# R2P_BLDC_module.net
KiCad netlist of a schematic drawn in EAGLE
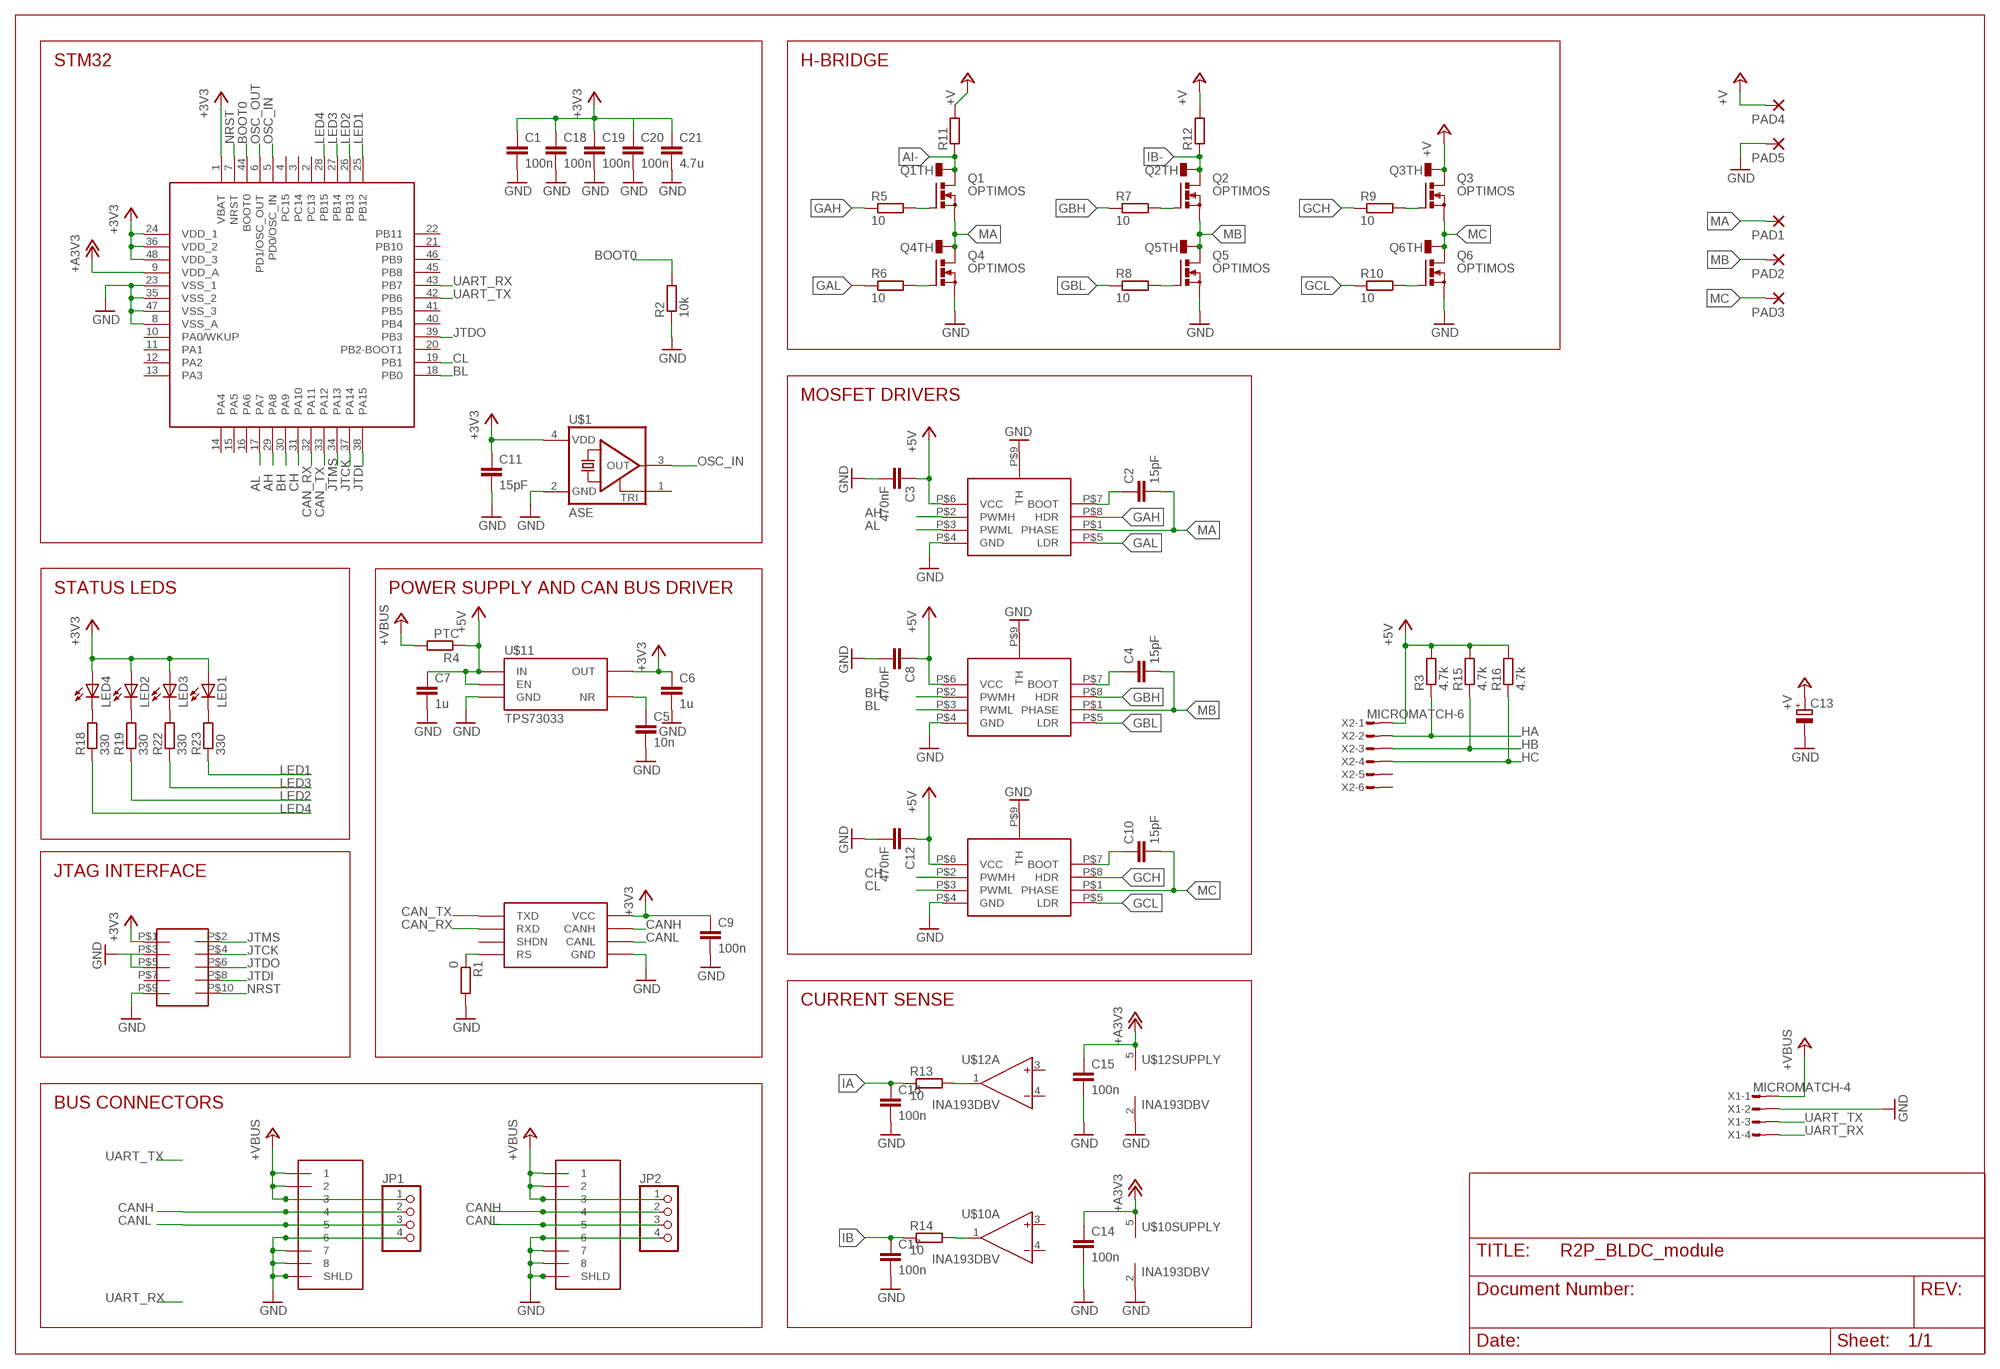
[diagram p0: schematic, sheet 1]

(export (version "E")
  (design (tool "Eeschema 10.0.6"))
  (components
    (comp (ref "1")
      (value "RJ45-43860")
      (footprint "eagle-import:0438600010")
      (libsource (lib "eagle-import") (part "RJ45-43860"))
    )
    (comp (ref "2")
      (value "RJ45-43860")
      (footprint "eagle-import:0438600010")
      (libsource (lib "eagle-import") (part "RJ45-43860"))
    )
    (comp (ref "C1")
      (value "100n")
      (footprint "eagle-import:C0603")
      (libsource (lib "eagle-import") (part "C-EUC0603"))
    )
    (comp (ref "C2")
      (value "15pF")
      (footprint "eagle-import:C0603")
      (libsource (lib "eagle-import") (part "C-EUC0603"))
    )
    (comp (ref "C3")
      (value "470nF")
      (footprint "eagle-import:C0603")
      (libsource (lib "eagle-import") (part "C-EUC0603"))
    )
    (comp (ref "C4")
      (value "15pF")
      (footprint "eagle-import:C0603")
      (libsource (lib "eagle-import") (part "C-EUC0603"))
    )
    (comp (ref "C5")
      (value "10n")
      (footprint "eagle-import:C0603")
      (libsource (lib "eagle-import") (part "C-EUC0603"))
    )
    (comp (ref "C6")
      (value "1u")
      (footprint "eagle-import:C0603")
      (libsource (lib "eagle-import") (part "C-EUC0603"))
    )
    (comp (ref "C7")
      (value "1u")
      (footprint "eagle-import:C0603")
      (libsource (lib "eagle-import") (part "C-EUC0603"))
    )
    (comp (ref "C8")
      (value "470nF")
      (footprint "eagle-import:C0603")
      (libsource (lib "eagle-import") (part "C-EUC0603"))
    )
    (comp (ref "C9")
      (value "100n")
      (footprint "eagle-import:C0603")
      (libsource (lib "eagle-import") (part "C-EUC0603"))
    )
    (comp (ref "C10")
      (value "15pF")
      (footprint "eagle-import:C0603")
      (libsource (lib "eagle-import") (part "C-EUC0603"))
    )
    (comp (ref "C11")
      (value "15pF")
      (footprint "eagle-import:C0603")
      (libsource (lib "eagle-import") (part "C-EUC0603"))
    )
    (comp (ref "C12")
      (value "470nF")
      (footprint "eagle-import:C0603")
      (libsource (lib "eagle-import") (part "C-EUC0603"))
    )
    (comp (ref "C13")
      (value "CPOL-EUE35-12AXIAL")
      (footprint "eagle-import:E35-12")
      (libsource (lib "eagle-import") (part "CPOL-EUE35-12AXIAL"))
    )
    (comp (ref "C14")
      (value "100n")
      (footprint "eagle-import:C0603")
      (libsource (lib "eagle-import") (part "C-EUC0603"))
    )
    (comp (ref "C15")
      (value "100n")
      (footprint "eagle-import:C0603")
      (libsource (lib "eagle-import") (part "C-EUC0603"))
    )
    (comp (ref "C16")
      (value "100n")
      (footprint "eagle-import:C0603")
      (libsource (lib "eagle-import") (part "C-EUC0603"))
    )
    (comp (ref "C17")
      (value "100n")
      (footprint "eagle-import:C0603")
      (libsource (lib "eagle-import") (part "C-EUC0603"))
    )
    (comp (ref "C18")
      (value "100n")
      (footprint "eagle-import:C0603")
      (libsource (lib "eagle-import") (part "C-EUC0603"))
    )
    (comp (ref "C19")
      (value "100n")
      (footprint "eagle-import:C0603")
      (libsource (lib "eagle-import") (part "C-EUC0603"))
    )
    (comp (ref "C20")
      (value "100n")
      (footprint "eagle-import:C0603")
      (libsource (lib "eagle-import") (part "C-EUC0603"))
    )
    (comp (ref "C21")
      (value "4.7u")
      (footprint "eagle-import:C0805")
      (libsource (lib "eagle-import") (part "C-EUC0805"))
    )
    (comp (ref "JP1")
      (value "PINHD-1X4")
      (footprint "eagle-import:1X04")
      (libsource (lib "eagle-import") (part "PINHD-1X4"))
    )
    (comp (ref "JP2")
      (value "PINHD-1X4")
      (footprint "eagle-import:1X04")
      (libsource (lib "eagle-import") (part "PINHD-1X4"))
    )
    (comp (ref "LED1")
      (value "LEDCHIPLED_0805")
      (footprint "eagle-import:CHIPLED_0805")
      (libsource (lib "eagle-import") (part "LEDCHIPLED_0805"))
    )
    (comp (ref "LED2")
      (value "LEDCHIPLED_0805")
      (footprint "eagle-import:CHIPLED_0805")
      (libsource (lib "eagle-import") (part "LEDCHIPLED_0805"))
    )
    (comp (ref "LED3")
      (value "LEDCHIPLED_0805")
      (footprint "eagle-import:CHIPLED_0805")
      (libsource (lib "eagle-import") (part "LEDCHIPLED_0805"))
    )
    (comp (ref "LED4")
      (value "LEDCHIPLED_0805")
      (footprint "eagle-import:CHIPLED_0805")
      (libsource (lib "eagle-import") (part "LEDCHIPLED_0805"))
    )
    (comp (ref "PAD1")
      (value "3,81/1,4")
      (footprint "eagle-import:3,81_1,4")
      (libsource (lib "eagle-import") (part "3,81/1,4"))
    )
    (comp (ref "PAD2")
      (value "3,81/1,4")
      (footprint "eagle-import:3,81_1,4")
      (libsource (lib "eagle-import") (part "3,81/1,4"))
    )
    (comp (ref "PAD3")
      (value "3,81/1,4")
      (footprint "eagle-import:3,81_1,4")
      (libsource (lib "eagle-import") (part "3,81/1,4"))
    )
    (comp (ref "PAD4")
      (value "3,81/1,4")
      (footprint "eagle-import:3,81_1,4")
      (libsource (lib "eagle-import") (part "3,81/1,4"))
    )
    (comp (ref "PAD5")
      (value "3,81/1,4")
      (footprint "eagle-import:3,81_1,4")
      (libsource (lib "eagle-import") (part "3,81/1,4"))
    )
    (comp (ref "Q1")
      (value "OPTIMOS")
      (footprint "eagle-import:PG-TDSON-8")
      (libsource (lib "eagle-import") (part "OPTIMOS"))
    )
    (comp (ref "Q2")
      (value "OPTIMOS")
      (footprint "eagle-import:PG-TDSON-8")
      (libsource (lib "eagle-import") (part "OPTIMOS"))
    )
    (comp (ref "Q3")
      (value "OPTIMOS")
      (footprint "eagle-import:PG-TDSON-8")
      (libsource (lib "eagle-import") (part "OPTIMOS"))
    )
    (comp (ref "Q4")
      (value "OPTIMOS")
      (footprint "eagle-import:PG-TDSON-8")
      (libsource (lib "eagle-import") (part "OPTIMOS"))
    )
    (comp (ref "Q5")
      (value "OPTIMOS")
      (footprint "eagle-import:PG-TDSON-8")
      (libsource (lib "eagle-import") (part "OPTIMOS"))
    )
    (comp (ref "Q6")
      (value "OPTIMOS")
      (footprint "eagle-import:PG-TDSON-8")
      (libsource (lib "eagle-import") (part "OPTIMOS"))
    )
    (comp (ref "R1")
      (value "0")
      (footprint "eagle-import:R0603")
      (libsource (lib "eagle-import") (part "R-EU_R0603"))
    )
    (comp (ref "R2")
      (value "10k")
      (footprint "eagle-import:R0603")
      (libsource (lib "eagle-import") (part "R-EU_R0603"))
    )
    (comp (ref "R3")
      (value "4.7k")
      (footprint "eagle-import:R0603")
      (libsource (lib "eagle-import") (part "R-EU_R0603"))
    )
    (comp (ref "R4")
      (value "PTC")
      (footprint "eagle-import:R0805")
      (libsource (lib "eagle-import") (part "R-EU_R0805"))
    )
    (comp (ref "R5")
      (value "10")
      (footprint "eagle-import:R0603")
      (libsource (lib "eagle-import") (part "R-EU_R0603"))
    )
    (comp (ref "R6")
      (value "10")
      (footprint "eagle-import:R0603")
      (libsource (lib "eagle-import") (part "R-EU_R0603"))
    )
    (comp (ref "R7")
      (value "10")
      (footprint "eagle-import:R0603")
      (libsource (lib "eagle-import") (part "R-EU_R0603"))
    )
    (comp (ref "R8")
      (value "10")
      (footprint "eagle-import:R0603")
      (libsource (lib "eagle-import") (part "R-EU_R0603"))
    )
    (comp (ref "R9")
      (value "10")
      (footprint "eagle-import:R0603")
      (libsource (lib "eagle-import") (part "R-EU_R0603"))
    )
    (comp (ref "R10")
      (value "10")
      (footprint "eagle-import:R0603")
      (libsource (lib "eagle-import") (part "R-EU_R0603"))
    )
    (comp (ref "R11")
      (value "R-EU_R1206")
      (footprint "eagle-import:R1206")
      (libsource (lib "eagle-import") (part "R-EU_R1206"))
    )
    (comp (ref "R12")
      (value "R-EU_R1206")
      (footprint "eagle-import:R1206")
      (libsource (lib "eagle-import") (part "R-EU_R1206"))
    )
    (comp (ref "R13")
      (value "10")
      (footprint "eagle-import:R0603")
      (libsource (lib "eagle-import") (part "R-EU_R0603"))
    )
    (comp (ref "R14")
      (value "10")
      (footprint "eagle-import:R0603")
      (libsource (lib "eagle-import") (part "R-EU_R0603"))
    )
    (comp (ref "R15")
      (value "4.7k")
      (footprint "eagle-import:R0603")
      (libsource (lib "eagle-import") (part "R-EU_R0603"))
    )
    (comp (ref "R16")
      (value "4.7k")
      (footprint "eagle-import:R0603")
      (libsource (lib "eagle-import") (part "R-EU_R0603"))
    )
    (comp (ref "R18")
      (value "330")
      (footprint "eagle-import:R0603")
      (libsource (lib "eagle-import") (part "R-EU_R0603"))
    )
    (comp (ref "R19")
      (value "330")
      (footprint "eagle-import:R0603")
      (libsource (lib "eagle-import") (part "R-EU_R0603"))
    )
    (comp (ref "R22")
      (value "330")
      (footprint "eagle-import:R0603")
      (libsource (lib "eagle-import") (part "R-EU_R0603"))
    )
    (comp (ref "R23")
      (value "330")
      (footprint "eagle-import:R0603")
      (libsource (lib "eagle-import") (part "R-EU_R0603"))
    )
    (comp (ref "SOT1")
      (value "MAX3051")
      (footprint "eagle-import:SOT23-8L")
      (libsource (lib "eagle-import") (part "MAX3051"))
    )
    (comp (ref "U$1")
      (value "ASE")
      (footprint "eagle-import:ASE")
      (libsource (lib "eagle-import") (part "ASE"))
    )
    (comp (ref "U$2")
      (value "MCP14700MF")
      (footprint "eagle-import:DFN8")
      (libsource (lib "eagle-import") (part "MCP14700MF"))
    )
    (comp (ref "U$4")
      (value "FTSH-105")
      (footprint "eagle-import:FTSH-105")
      (libsource (lib "eagle-import") (part "FTSH-105"))
    )
    (comp (ref "U$8")
      (value "MCP14700MF")
      (footprint "eagle-import:DFN8")
      (libsource (lib "eagle-import") (part "MCP14700MF"))
    )
    (comp (ref "U$9")
      (value "MCP14700MF")
      (footprint "eagle-import:DFN8")
      (libsource (lib "eagle-import") (part "MCP14700MF"))
    )
    (comp (ref "U$10")
      (value "INA193DBV")
      (footprint "eagle-import:SOT23-5L")
      (libsource (lib "eagle-import") (part "INA193DBV"))
    )
    (comp (ref "U$11")
      (value "TPS73033")
      (footprint "eagle-import:SOT23-5L")
      (libsource (lib "eagle-import") (part "TPS73033"))
    )
    (comp (ref "U$12")
      (value "INA193DBV")
      (footprint "eagle-import:SOT23-5L")
      (libsource (lib "eagle-import") (part "INA193DBV"))
    )
    (comp (ref "U1")
      (value "STM32F103CX")
      (footprint "eagle-import:LQFP48")
      (libsource (lib "eagle-import") (part "STM32F103CX"))
    )
    (comp (ref "X1")
      (value "MICROMATCH-4")
      (footprint "eagle-import:MICROMATCH-4")
      (libsource (lib "eagle-import") (part "MICROMATCH-4"))
    )
    (comp (ref "X2")
      (value "MICROMATCH-6")
      (footprint "eagle-import:MICROMATCH-6")
      (libsource (lib "eagle-import") (part "MICROMATCH-6"))
    )
  )
  (nets
    (net (code "1") (name "+3V3") (class "Default")
      (node (ref "C1") (pin "1") (pinfunction "1_1") (pintype "passive"))
      (node (ref "C11") (pin "1") (pinfunction "1_1") (pintype "passive"))
      (node (ref "C18") (pin "1") (pinfunction "1_1") (pintype "passive"))
      (node (ref "C19") (pin "1") (pinfunction "1_1") (pintype "passive"))
      (node (ref "C20") (pin "1") (pinfunction "1_1") (pintype "passive"))
      (node (ref "C21") (pin "1") (pinfunction "1_1") (pintype "passive"))
      (node (ref "C6") (pin "1") (pinfunction "1_1") (pintype "passive"))
      (node (ref "C9") (pin "1") (pinfunction "1_1") (pintype "passive"))
      (node (ref "LED1") (pin "A") (pinfunction "A_A") (pintype "passive"))
      (node (ref "LED2") (pin "A") (pinfunction "A_A") (pintype "passive"))
      (node (ref "LED3") (pin "A") (pinfunction "A_A") (pintype "passive"))
      (node (ref "LED4") (pin "A") (pinfunction "A_A") (pintype "passive"))
      (node (ref "SOT1") (pin "P$3") (pinfunction "VCC_P$3") (pintype "bidirectional"))
      (node (ref "U$1") (pin "4") (pinfunction "VDD_4") (pintype "power_in"))
      (node (ref "U$11") (pin "5") (pinfunction "OUT_5") (pintype "power_in"))
      (node (ref "U$4") (pin "P$1") (pinfunction "P$1_P$1") (pintype "bidirectional"))
      (node (ref "U1") (pin "1") (pinfunction "VBAT_1") (pintype "bidirectional"))
      (node (ref "U1") (pin "24") (pinfunction "VDD_1_24") (pintype "bidirectional"))
      (node (ref "U1") (pin "36") (pinfunction "VDD_2_36") (pintype "bidirectional"))
      (node (ref "U1") (pin "48") (pinfunction "VDD_3_48") (pintype "bidirectional"))
    )
    (net (code "2") (name "+5V") (class "Default")
      (node (ref "C12") (pin "1") (pinfunction "1_1") (pintype "passive"))
      (node (ref "C3") (pin "1") (pinfunction "1_1") (pintype "passive"))
      (node (ref "C7") (pin "1") (pinfunction "1_1") (pintype "passive"))
      (node (ref "C8") (pin "1") (pinfunction "1_1") (pintype "passive"))
      (node (ref "R15") (pin "2") (pinfunction "2_2") (pintype "passive"))
      (node (ref "R16") (pin "2") (pinfunction "2_2") (pintype "passive"))
      (node (ref "R3") (pin "2") (pinfunction "2_2") (pintype "passive"))
      (node (ref "R4") (pin "1") (pinfunction "1_1") (pintype "passive"))
      (node (ref "U$11") (pin "1") (pinfunction "IN_1") (pintype "power_in"))
      (node (ref "U$11") (pin "3") (pinfunction "EN_3") (pintype "bidirectional"))
      (node (ref "U$2") (pin "P$6") (pinfunction "VCC_P$6") (pintype "bidirectional"))
      (node (ref "U$8") (pin "P$6") (pinfunction "VCC_P$6") (pintype "bidirectional"))
      (node (ref "U$9") (pin "P$6") (pinfunction "VCC_P$6") (pintype "bidirectional"))
      (node (ref "X2") (pin "1") (pinfunction "S_1") (pintype "passive"))
    )
    (net (code "3") (name "+A3V3") (class "Default")
      (node (ref "C14") (pin "1") (pinfunction "1_1") (pintype "passive"))
      (node (ref "C15") (pin "1") (pinfunction "1_1") (pintype "passive"))
      (node (ref "U$10") (pin "5") (pinfunction "V+_5") (pintype "power_in"))
      (node (ref "U$12") (pin "5") (pinfunction "V+_5") (pintype "power_in"))
      (node (ref "U1") (pin "9") (pinfunction "VDD_A_9") (pintype "bidirectional"))
    )
    (net (code "4") (name "+V") (class "Default")
      (node (ref "C13") (pin "+") (pinfunction "+_+") (pintype "passive"))
      (node (ref "PAD4") (pin "1") (pinfunction "P_1") (pintype "passive"))
      (node (ref "Q3") (pin "5") (pinfunction "D_5") (pintype "passive"))
      (node (ref "Q3") (pin "6") (pinfunction "D_6") (pintype "passive"))
      (node (ref "Q3") (pin "7") (pinfunction "D_7") (pintype "passive"))
      (node (ref "Q3") (pin "8") (pinfunction "D_8") (pintype "passive"))
      (node (ref "Q3") (pin "TH") (pinfunction "TH_TH") (pintype "passive"))
      (node (ref "R11") (pin "2") (pinfunction "2_2") (pintype "passive"))
      (node (ref "R12") (pin "2") (pinfunction "2_2") (pintype "passive"))
    )
    (net (code "5") (name "+VBUS") (class "Default")
      (node (ref "1") (pin "P$1") (pinfunction "1_P$1") (pintype "bidirectional"))
      (node (ref "1") (pin "P$2") (pinfunction "2_P$2") (pintype "bidirectional"))
      (node (ref "1") (pin "P$3") (pinfunction "3_P$3") (pintype "bidirectional"))
      (node (ref "2") (pin "P$1") (pinfunction "1_P$1") (pintype "bidirectional"))
      (node (ref "2") (pin "P$2") (pinfunction "2_P$2") (pintype "bidirectional"))
      (node (ref "2") (pin "P$3") (pinfunction "3_P$3") (pintype "bidirectional"))
      (node (ref "JP1") (pin "1") (pinfunction "1_1") (pintype "passive"))
      (node (ref "JP2") (pin "1") (pinfunction "1_1") (pintype "passive"))
      (node (ref "R4") (pin "2") (pinfunction "2_2") (pintype "passive"))
      (node (ref "X1") (pin "1") (pinfunction "S_1") (pintype "passive"))
    )
    (net (code "6") (name "/AH") (class "Default")
      (node (ref "U$2") (pin "P$2") (pinfunction "PWMH_P$2") (pintype "bidirectional"))
      (node (ref "U1") (pin "29") (pinfunction "PA8_29") (pintype "bidirectional"))
    )
    (net (code "7") (name "/AL") (class "Default")
      (node (ref "U$2") (pin "P$3") (pinfunction "PWML_P$3") (pintype "bidirectional"))
      (node (ref "U1") (pin "17") (pinfunction "PA7_17") (pintype "bidirectional"))
    )
    (net (code "8") (name "/BH") (class "Default")
      (node (ref "U$8") (pin "P$2") (pinfunction "PWMH_P$2") (pintype "bidirectional"))
      (node (ref "U1") (pin "30") (pinfunction "PA9_30") (pintype "bidirectional"))
    )
    (net (code "9") (name "/BL") (class "Default")
      (node (ref "U$8") (pin "P$3") (pinfunction "PWML_P$3") (pintype "bidirectional"))
      (node (ref "U1") (pin "18") (pinfunction "PB0_18") (pintype "bidirectional"))
    )
    (net (code "10") (name "/BOOT0") (class "Default")
      (node (ref "R2") (pin "2") (pinfunction "2_2") (pintype "passive"))
      (node (ref "U1") (pin "44") (pinfunction "BOOT0_44") (pintype "bidirectional"))
    )
    (net (code "11") (name "/CANH") (class "Default")
      (node (ref "1") (pin "P$4") (pinfunction "4_P$4") (pintype "bidirectional"))
      (node (ref "2") (pin "P$4") (pinfunction "4_P$4") (pintype "bidirectional"))
      (node (ref "JP1") (pin "2") (pinfunction "2_2") (pintype "passive"))
      (node (ref "JP2") (pin "2") (pinfunction "2_2") (pintype "passive"))
      (node (ref "SOT1") (pin "P$7") (pinfunction "CANH_P$7") (pintype "bidirectional"))
    )
    (net (code "12") (name "/CANL") (class "Default")
      (node (ref "1") (pin "P$5") (pinfunction "5_P$5") (pintype "bidirectional"))
      (node (ref "2") (pin "P$5") (pinfunction "5_P$5") (pintype "bidirectional"))
      (node (ref "JP1") (pin "3") (pinfunction "3_3") (pintype "passive"))
      (node (ref "JP2") (pin "3") (pinfunction "3_3") (pintype "passive"))
      (node (ref "SOT1") (pin "P$6") (pinfunction "CANL_P$6") (pintype "bidirectional"))
    )
    (net (code "13") (name "/CAN_RX") (class "Default")
      (node (ref "SOT1") (pin "P$4") (pinfunction "RXD_P$4") (pintype "bidirectional"))
      (node (ref "U1") (pin "32") (pinfunction "PA11_32") (pintype "bidirectional"))
    )
    (net (code "14") (name "/CAN_TX") (class "Default")
      (node (ref "SOT1") (pin "P$1") (pinfunction "TXD_P$1") (pintype "bidirectional"))
      (node (ref "U1") (pin "33") (pinfunction "PA12_33") (pintype "bidirectional"))
    )
    (net (code "15") (name "/CH") (class "Default")
      (node (ref "U$9") (pin "P$2") (pinfunction "PWMH_P$2") (pintype "bidirectional"))
      (node (ref "U1") (pin "31") (pinfunction "PA10_31") (pintype "bidirectional"))
    )
    (net (code "16") (name "/CL") (class "Default")
      (node (ref "U$9") (pin "P$3") (pinfunction "PWML_P$3") (pintype "bidirectional"))
      (node (ref "U1") (pin "19") (pinfunction "PB1_19") (pintype "bidirectional"))
    )
    (net (code "17") (name "/HA") (class "Default")
      (node (ref "R3") (pin "1") (pinfunction "1_1") (pintype "passive"))
      (node (ref "X2") (pin "2") (pinfunction "S_2") (pintype "passive"))
    )
    (net (code "18") (name "/HB") (class "Default")
      (node (ref "R15") (pin "1") (pinfunction "1_1") (pintype "passive"))
      (node (ref "X2") (pin "3") (pinfunction "S_3") (pintype "passive"))
    )
    (net (code "19") (name "/HC") (class "Default")
      (node (ref "R16") (pin "1") (pinfunction "1_1") (pintype "passive"))
      (node (ref "X2") (pin "4") (pinfunction "S_4") (pintype "passive"))
    )
    (net (code "20") (name "/JTCK") (class "Default")
      (node (ref "U$4") (pin "P$4") (pinfunction "P$4_P$4") (pintype "bidirectional"))
      (node (ref "U1") (pin "37") (pinfunction "PA14_37") (pintype "bidirectional"))
    )
    (net (code "21") (name "/JTDI") (class "Default")
      (node (ref "U$4") (pin "P$8") (pinfunction "P$8_P$8") (pintype "bidirectional"))
      (node (ref "U1") (pin "38") (pinfunction "PA15_38") (pintype "bidirectional"))
    )
    (net (code "22") (name "/JTDO") (class "Default")
      (node (ref "U$4") (pin "P$6") (pinfunction "P$6_P$6") (pintype "bidirectional"))
      (node (ref "U1") (pin "39") (pinfunction "PB3_39") (pintype "bidirectional"))
    )
    (net (code "23") (name "/JTMS") (class "Default")
      (node (ref "U$4") (pin "P$2") (pinfunction "P$2_P$2") (pintype "bidirectional"))
      (node (ref "U1") (pin "34") (pinfunction "PA13_34") (pintype "bidirectional"))
    )
    (net (code "24") (name "/LED1") (class "Default")
      (node (ref "R23") (pin "1") (pinfunction "1_1") (pintype "passive"))
      (node (ref "U1") (pin "25") (pinfunction "PB12_25") (pintype "bidirectional"))
    )
    (net (code "25") (name "/LED2") (class "Default")
      (node (ref "R19") (pin "1") (pinfunction "1_1") (pintype "passive"))
      (node (ref "U1") (pin "26") (pinfunction "PB13_26") (pintype "bidirectional"))
    )
    (net (code "26") (name "/LED3") (class "Default")
      (node (ref "R22") (pin "1") (pinfunction "1_1") (pintype "passive"))
      (node (ref "U1") (pin "27") (pinfunction "PB14_27") (pintype "bidirectional"))
    )
    (net (code "27") (name "/LED4") (class "Default")
      (node (ref "R18") (pin "1") (pinfunction "1_1") (pintype "passive"))
      (node (ref "U1") (pin "28") (pinfunction "PB15_28") (pintype "bidirectional"))
    )
    (net (code "28") (name "/NRST") (class "Default")
      (node (ref "U$4") (pin "P$10") (pinfunction "P$10_P$10") (pintype "bidirectional"))
      (node (ref "U1") (pin "7") (pinfunction "NRST_7") (pintype "bidirectional"))
    )
    (net (code "29") (name "/OSC_IN") (class "Default")
      (node (ref "U$1") (pin "3") (pinfunction "OUT_3") (pintype "output"))
      (node (ref "U1") (pin "5") (pinfunction "PD0/OSC_IN_5") (pintype "bidirectional"))
    )
    (net (code "30") (name "/OSC_OUT") (class "Default")
      (node (ref "U1") (pin "6") (pinfunction "PD1/OSC_OUT_6") (pintype "bidirectional"))
    )
    (net (code "31") (name "/UART_RX") (class "Default")
      (node (ref "U1") (pin "43") (pinfunction "PB7_43") (pintype "bidirectional"))
      (node (ref "X1") (pin "4") (pinfunction "S_4") (pintype "passive"))
    )
    (net (code "32") (name "/UART_TX") (class "Default")
      (node (ref "U1") (pin "42") (pinfunction "PB6_42") (pintype "bidirectional"))
      (node (ref "X1") (pin "3") (pinfunction "S_3") (pintype "passive"))
    )
    (net (code "33") (name "AI-") (class "Default")
      (node (ref "Q1") (pin "5") (pinfunction "D_5") (pintype "passive"))
      (node (ref "Q1") (pin "6") (pinfunction "D_6") (pintype "passive"))
      (node (ref "Q1") (pin "7") (pinfunction "D_7") (pintype "passive"))
      (node (ref "Q1") (pin "8") (pinfunction "D_8") (pintype "passive"))
      (node (ref "Q1") (pin "TH") (pinfunction "TH_TH") (pintype "passive"))
      (node (ref "R11") (pin "1") (pinfunction "1_1") (pintype "passive"))
    )
    (net (code "34") (name "GAH") (class "Default")
      (node (ref "R5") (pin "1") (pinfunction "1_1") (pintype "passive"))
      (node (ref "U$2") (pin "P$8") (pinfunction "HDR_P$8") (pintype "bidirectional"))
    )
    (net (code "35") (name "GAL") (class "Default")
      (node (ref "R6") (pin "1") (pinfunction "1_1") (pintype "passive"))
      (node (ref "U$2") (pin "P$5") (pinfunction "LDR_P$5") (pintype "bidirectional"))
    )
    (net (code "36") (name "GBH") (class "Default")
      (node (ref "R7") (pin "1") (pinfunction "1_1") (pintype "passive"))
      (node (ref "U$8") (pin "P$8") (pinfunction "HDR_P$8") (pintype "bidirectional"))
    )
    (net (code "37") (name "GBL") (class "Default")
      (node (ref "R8") (pin "1") (pinfunction "1_1") (pintype "passive"))
      (node (ref "U$8") (pin "P$5") (pinfunction "LDR_P$5") (pintype "bidirectional"))
    )
    (net (code "38") (name "GCH") (class "Default")
      (node (ref "R9") (pin "1") (pinfunction "1_1") (pintype "passive"))
      (node (ref "U$9") (pin "P$8") (pinfunction "HDR_P$8") (pintype "bidirectional"))
    )
    (net (code "39") (name "GCL") (class "Default")
      (node (ref "R10") (pin "1") (pinfunction "1_1") (pintype "passive"))
      (node (ref "U$9") (pin "P$5") (pinfunction "LDR_P$5") (pintype "bidirectional"))
    )
    (net (code "40") (name "GND") (class "Default")
      (node (ref "1") (pin "P$10") (pinfunction "P$1_P$10") (pintype "power_in"))
      (node (ref "1") (pin "P$6") (pinfunction "6_P$6") (pintype "bidirectional"))
      (node (ref "1") (pin "P$7") (pinfunction "7_P$7") (pintype "bidirectional"))
      (node (ref "1") (pin "P$8") (pinfunction "8_P$8") (pintype "bidirectional"))
      (node (ref "1") (pin "P$9") (pinfunction "SHLD_P$9") (pintype "power_in"))
      (node (ref "2") (pin "P$10") (pinfunction "P$1_P$10") (pintype "power_in"))
      (node (ref "2") (pin "P$6") (pinfunction "6_P$6") (pintype "bidirectional"))
      (node (ref "2") (pin "P$7") (pinfunction "7_P$7") (pintype "bidirectional"))
      (node (ref "2") (pin "P$8") (pinfunction "8_P$8") (pintype "bidirectional"))
      (node (ref "2") (pin "P$9") (pinfunction "SHLD_P$9") (pintype "power_in"))
      (node (ref "C1") (pin "2") (pinfunction "2_2") (pintype "passive"))
      (node (ref "C11") (pin "2") (pinfunction "2_2") (pintype "passive"))
      (node (ref "C12") (pin "2") (pinfunction "2_2") (pintype "passive"))
      (node (ref "C13") (pin "-") (pinfunction "-_-") (pintype "passive"))
      (node (ref "C14") (pin "2") (pinfunction "2_2") (pintype "passive"))
      (node (ref "C15") (pin "2") (pinfunction "2_2") (pintype "passive"))
      (node (ref "C16") (pin "2") (pinfunction "2_2") (pintype "passive"))
      (node (ref "C17") (pin "2") (pinfunction "2_2") (pintype "passive"))
      (node (ref "C18") (pin "2") (pinfunction "2_2") (pintype "passive"))
      (node (ref "C19") (pin "2") (pinfunction "2_2") (pintype "passive"))
      (node (ref "C20") (pin "2") (pinfunction "2_2") (pintype "passive"))
      (node (ref "C21") (pin "2") (pinfunction "2_2") (pintype "passive"))
      (node (ref "C3") (pin "2") (pinfunction "2_2") (pintype "passive"))
      (node (ref "C5") (pin "2") (pinfunction "2_2") (pintype "passive"))
      (node (ref "C6") (pin "2") (pinfunction "2_2") (pintype "passive"))
      (node (ref "C7") (pin "2") (pinfunction "2_2") (pintype "passive"))
      (node (ref "C8") (pin "2") (pinfunction "2_2") (pintype "passive"))
      (node (ref "C9") (pin "2") (pinfunction "2_2") (pintype "passive"))
      (node (ref "JP1") (pin "4") (pinfunction "4_4") (pintype "passive"))
      (node (ref "JP2") (pin "4") (pinfunction "4_4") (pintype "passive"))
      (node (ref "PAD5") (pin "1") (pinfunction "P_1") (pintype "passive"))
      (node (ref "Q4") (pin "1") (pinfunction "S_1") (pintype "passive"))
      (node (ref "Q4") (pin "2") (pinfunction "S_2") (pintype "passive"))
      (node (ref "Q4") (pin "3") (pinfunction "S_3") (pintype "passive"))
      (node (ref "Q5") (pin "1") (pinfunction "S_1") (pintype "passive"))
      (node (ref "Q5") (pin "2") (pinfunction "S_2") (pintype "passive"))
      (node (ref "Q5") (pin "3") (pinfunction "S_3") (pintype "passive"))
      (node (ref "Q6") (pin "1") (pinfunction "S_1") (pintype "passive"))
      (node (ref "Q6") (pin "2") (pinfunction "S_2") (pintype "passive"))
      (node (ref "Q6") (pin "3") (pinfunction "S_3") (pintype "passive"))
      (node (ref "R1") (pin "2") (pinfunction "2_2") (pintype "passive"))
      (node (ref "R2") (pin "1") (pinfunction "1_1") (pintype "passive"))
      (node (ref "SOT1") (pin "P$2") (pinfunction "GND_P$2") (pintype "bidirectional"))
      (node (ref "U$1") (pin "2") (pinfunction "GND_2") (pintype "power_in"))
      (node (ref "U$10") (pin "2") (pinfunction "V-_2") (pintype "power_in"))
      (node (ref "U$11") (pin "2") (pinfunction "GND_2") (pintype "power_in"))
      (node (ref "U$12") (pin "2") (pinfunction "V-_2") (pintype "power_in"))
      (node (ref "U$2") (pin "P$4") (pinfunction "GND_P$4") (pintype "bidirectional"))
      (node (ref "U$2") (pin "P$9") (pinfunction "TH_P$9") (pintype "bidirectional"))
      (node (ref "U$4") (pin "P$3") (pinfunction "P$3_P$3") (pintype "bidirectional"))
      (node (ref "U$4") (pin "P$9") (pinfunction "P$9_P$9") (pintype "bidirectional"))
      (node (ref "U$8") (pin "P$4") (pinfunction "GND_P$4") (pintype "bidirectional"))
      (node (ref "U$8") (pin "P$9") (pinfunction "TH_P$9") (pintype "bidirectional"))
      (node (ref "U$9") (pin "P$4") (pinfunction "GND_P$4") (pintype "bidirectional"))
      (node (ref "U$9") (pin "P$9") (pinfunction "TH_P$9") (pintype "bidirectional"))
      (node (ref "U1") (pin "23") (pinfunction "VSS_1_23") (pintype "bidirectional"))
      (node (ref "U1") (pin "35") (pinfunction "VSS_2_35") (pintype "bidirectional"))
      (node (ref "U1") (pin "47") (pinfunction "VSS_3_47") (pintype "bidirectional"))
      (node (ref "U1") (pin "8") (pinfunction "VSS_A_8") (pintype "bidirectional"))
      (node (ref "X1") (pin "2") (pinfunction "S_2") (pintype "passive"))
    )
    (net (code "41") (name "IA") (class "Default")
      (node (ref "C16") (pin "1") (pinfunction "1_1") (pintype "passive"))
      (node (ref "R13") (pin "1") (pinfunction "1_1") (pintype "passive"))
    )
    (net (code "42") (name "IB") (class "Default")
      (node (ref "C17") (pin "1") (pinfunction "1_1") (pintype "passive"))
      (node (ref "R14") (pin "1") (pinfunction "1_1") (pintype "passive"))
    )
    (net (code "43") (name "IB-") (class "Default")
      (node (ref "Q2") (pin "5") (pinfunction "D_5") (pintype "passive"))
      (node (ref "Q2") (pin "6") (pinfunction "D_6") (pintype "passive"))
      (node (ref "Q2") (pin "7") (pinfunction "D_7") (pintype "passive"))
      (node (ref "Q2") (pin "8") (pinfunction "D_8") (pintype "passive"))
      (node (ref "Q2") (pin "TH") (pinfunction "TH_TH") (pintype "passive"))
      (node (ref "R12") (pin "1") (pinfunction "1_1") (pintype "passive"))
    )
    (net (code "44") (name "MA") (class "Default")
      (node (ref "C2") (pin "2") (pinfunction "2_2") (pintype "passive"))
      (node (ref "PAD1") (pin "1") (pinfunction "P_1") (pintype "passive"))
      (node (ref "Q1") (pin "1") (pinfunction "S_1") (pintype "passive"))
      (node (ref "Q1") (pin "2") (pinfunction "S_2") (pintype "passive"))
      (node (ref "Q1") (pin "3") (pinfunction "S_3") (pintype "passive"))
      (node (ref "Q4") (pin "5") (pinfunction "D_5") (pintype "passive"))
      (node (ref "Q4") (pin "6") (pinfunction "D_6") (pintype "passive"))
      (node (ref "Q4") (pin "7") (pinfunction "D_7") (pintype "passive"))
      (node (ref "Q4") (pin "8") (pinfunction "D_8") (pintype "passive"))
      (node (ref "Q4") (pin "TH") (pinfunction "TH_TH") (pintype "passive"))
      (node (ref "U$2") (pin "P$1") (pinfunction "PHASE_P$1") (pintype "bidirectional"))
    )
    (net (code "45") (name "MB") (class "Default")
      (node (ref "C4") (pin "2") (pinfunction "2_2") (pintype "passive"))
      (node (ref "PAD2") (pin "1") (pinfunction "P_1") (pintype "passive"))
      (node (ref "Q2") (pin "1") (pinfunction "S_1") (pintype "passive"))
      (node (ref "Q2") (pin "2") (pinfunction "S_2") (pintype "passive"))
      (node (ref "Q2") (pin "3") (pinfunction "S_3") (pintype "passive"))
      (node (ref "Q5") (pin "5") (pinfunction "D_5") (pintype "passive"))
      (node (ref "Q5") (pin "6") (pinfunction "D_6") (pintype "passive"))
      (node (ref "Q5") (pin "7") (pinfunction "D_7") (pintype "passive"))
      (node (ref "Q5") (pin "8") (pinfunction "D_8") (pintype "passive"))
      (node (ref "Q5") (pin "TH") (pinfunction "TH_TH") (pintype "passive"))
      (node (ref "U$8") (pin "P$1") (pinfunction "PHASE_P$1") (pintype "bidirectional"))
    )
    (net (code "46") (name "MC") (class "Default")
      (node (ref "C10") (pin "2") (pinfunction "2_2") (pintype "passive"))
      (node (ref "PAD3") (pin "1") (pinfunction "P_1") (pintype "passive"))
      (node (ref "Q3") (pin "1") (pinfunction "S_1") (pintype "passive"))
      (node (ref "Q3") (pin "2") (pinfunction "S_2") (pintype "passive"))
      (node (ref "Q3") (pin "3") (pinfunction "S_3") (pintype "passive"))
      (node (ref "Q6") (pin "5") (pinfunction "D_5") (pintype "passive"))
      (node (ref "Q6") (pin "6") (pinfunction "D_6") (pintype "passive"))
      (node (ref "Q6") (pin "7") (pinfunction "D_7") (pintype "passive"))
      (node (ref "Q6") (pin "8") (pinfunction "D_8") (pintype "passive"))
      (node (ref "Q6") (pin "TH") (pinfunction "TH_TH") (pintype "passive"))
      (node (ref "U$9") (pin "P$1") (pinfunction "PHASE_P$1") (pintype "bidirectional"))
    )
    (net (code "47") (name "Net-(LED1-PadC)") (class "Default")
      (node (ref "LED1") (pin "C") (pinfunction "C_C") (pintype "passive"))
      (node (ref "R23") (pin "2") (pinfunction "2_2") (pintype "passive"))
    )
    (net (code "48") (name "Net-(LED2-PadC)") (class "Default")
      (node (ref "LED2") (pin "C") (pinfunction "C_C") (pintype "passive"))
      (node (ref "R19") (pin "2") (pinfunction "2_2") (pintype "passive"))
    )
    (net (code "49") (name "Net-(LED3-PadC)") (class "Default")
      (node (ref "LED3") (pin "C") (pinfunction "C_C") (pintype "passive"))
      (node (ref "R22") (pin "2") (pinfunction "2_2") (pintype "passive"))
    )
    (net (code "50") (name "Net-(LED4-PadC)") (class "Default")
      (node (ref "LED4") (pin "C") (pinfunction "C_C") (pintype "passive"))
      (node (ref "R18") (pin "2") (pinfunction "2_2") (pintype "passive"))
    )
    (net (code "51") (name "Net-(Q1A-G)") (class "Default")
      (node (ref "Q1") (pin "4") (pinfunction "G_4") (pintype "passive"))
      (node (ref "R5") (pin "2") (pinfunction "2_2") (pintype "passive"))
    )
    (net (code "52") (name "Net-(Q2A-G)") (class "Default")
      (node (ref "Q2") (pin "4") (pinfunction "G_4") (pintype "passive"))
      (node (ref "R7") (pin "2") (pinfunction "2_2") (pintype "passive"))
    )
    (net (code "53") (name "Net-(Q3A-G)") (class "Default")
      (node (ref "Q3") (pin "4") (pinfunction "G_4") (pintype "passive"))
      (node (ref "R9") (pin "2") (pinfunction "2_2") (pintype "passive"))
    )
    (net (code "54") (name "Net-(Q4A-G)") (class "Default")
      (node (ref "Q4") (pin "4") (pinfunction "G_4") (pintype "passive"))
      (node (ref "R6") (pin "2") (pinfunction "2_2") (pintype "passive"))
    )
    (net (code "55") (name "Net-(Q5A-G)") (class "Default")
      (node (ref "Q5") (pin "4") (pinfunction "G_4") (pintype "passive"))
      (node (ref "R8") (pin "2") (pinfunction "2_2") (pintype "passive"))
    )
    (net (code "56") (name "Net-(Q6A-G)") (class "Default")
      (node (ref "Q6") (pin "4") (pinfunction "G_4") (pintype "passive"))
      (node (ref "R10") (pin "2") (pinfunction "2_2") (pintype "passive"))
    )
    (net (code "57") (name "Net-(SOT1-RS)") (class "Default")
      (node (ref "R1") (pin "1") (pinfunction "1_1") (pintype "passive"))
      (node (ref "SOT1") (pin "P$8") (pinfunction "RS_P$8") (pintype "bidirectional"))
    )
    (net (code "58") (name "Net-(U$2-BOOT)") (class "Default")
      (node (ref "C2") (pin "1") (pinfunction "1_1") (pintype "passive"))
      (node (ref "U$2") (pin "P$7") (pinfunction "BOOT_P$7") (pintype "bidirectional"))
    )
    (net (code "59") (name "Net-(U$8-BOOT)") (class "Default")
      (node (ref "C4") (pin "1") (pinfunction "1_1") (pintype "passive"))
      (node (ref "U$8") (pin "P$7") (pinfunction "BOOT_P$7") (pintype "bidirectional"))
    )
    (net (code "60") (name "Net-(U$9-BOOT)") (class "Default")
      (node (ref "C10") (pin "1") (pinfunction "1_1") (pintype "passive"))
      (node (ref "U$9") (pin "P$7") (pinfunction "BOOT_P$7") (pintype "bidirectional"))
    )
    (net (code "61") (name "Net-(U$10A-OUT)") (class "Default")
      (node (ref "R14") (pin "2") (pinfunction "2_2") (pintype "passive"))
      (node (ref "U$10") (pin "1") (pinfunction "OUT_1") (pintype "output"))
    )
    (net (code "62") (name "Net-(U$11-NR)") (class "Default")
      (node (ref "C5") (pin "1") (pinfunction "1_1") (pintype "passive"))
      (node (ref "U$11") (pin "4") (pinfunction "NR_4") (pintype "bidirectional"))
    )
    (net (code "63") (name "Net-(U$12A-OUT)") (class "Default")
      (node (ref "R13") (pin "2") (pinfunction "2_2") (pintype "passive"))
      (node (ref "U$12") (pin "1") (pinfunction "OUT_1") (pintype "output"))
    )
    (net (code "64") (name "unconnected-(SOT1-SHDN-PadP$5)") (class "Default")
      (node (ref "SOT1") (pin "P$5") (pinfunction "SHDN_P$5") (pintype "bidirectional"))
    )
    (net (code "65") (name "unconnected-(U$1-TRI-Pad1)") (class "Default")
      (node (ref "U$1") (pin "1") (pinfunction "TRI_1") (pintype "input"))
    )
    (net (code "66") (name "unconnected-(U$4-PadP$5)") (class "Default")
      (node (ref "U$4") (pin "P$5") (pinfunction "P$5_P$5") (pintype "bidirectional"))
    )
    (net (code "67") (name "unconnected-(U$4-PadP$7)") (class "Default")
      (node (ref "U$4") (pin "P$7") (pinfunction "P$7_P$7") (pintype "bidirectional"))
    )
    (net (code "68") (name "unconnected-(U$10A-IN+-Pad3)") (class "Default")
      (node (ref "U$10") (pin "3") (pinfunction "IN+_3") (pintype "input"))
    )
    (net (code "69") (name "unconnected-(U$10A-IN--Pad4)") (class "Default")
      (node (ref "U$10") (pin "4") (pinfunction "IN-_4") (pintype "input"))
    )
    (net (code "70") (name "unconnected-(U$12A-IN+-Pad3)") (class "Default")
      (node (ref "U$12") (pin "3") (pinfunction "IN+_3") (pintype "input"))
    )
    (net (code "71") (name "unconnected-(U$12A-IN--Pad4)") (class "Default")
      (node (ref "U$12") (pin "4") (pinfunction "IN-_4") (pintype "input"))
    )
    (net (code "72") (name "unconnected-(U1-PA0{slash}WKUP-Pad10)") (class "Default")
      (node (ref "U1") (pin "10") (pinfunction "PA0/WKUP_10") (pintype "bidirectional"))
    )
    (net (code "73") (name "unconnected-(U1-PA1-Pad11)") (class "Default")
      (node (ref "U1") (pin "11") (pinfunction "PA1_11") (pintype "bidirectional"))
    )
    (net (code "74") (name "unconnected-(U1-PA2-Pad12)") (class "Default")
      (node (ref "U1") (pin "12") (pinfunction "PA2_12") (pintype "bidirectional"))
    )
    (net (code "75") (name "unconnected-(U1-PA3-Pad13)") (class "Default")
      (node (ref "U1") (pin "13") (pinfunction "PA3_13") (pintype "bidirectional"))
    )
    (net (code "76") (name "unconnected-(U1-PA4-Pad14)") (class "Default")
      (node (ref "U1") (pin "14") (pinfunction "PA4_14") (pintype "bidirectional"))
    )
    (net (code "77") (name "unconnected-(U1-PA5-Pad15)") (class "Default")
      (node (ref "U1") (pin "15") (pinfunction "PA5_15") (pintype "bidirectional"))
    )
    (net (code "78") (name "unconnected-(U1-PA6-Pad16)") (class "Default")
      (node (ref "U1") (pin "16") (pinfunction "PA6_16") (pintype "bidirectional"))
    )
    (net (code "79") (name "unconnected-(U1-PB2-BOOT1-Pad20)") (class "Default")
      (node (ref "U1") (pin "20") (pinfunction "PB2-BOOT1_20") (pintype "bidirectional"))
    )
    (net (code "80") (name "unconnected-(U1-PB4-Pad40)") (class "Default")
      (node (ref "U1") (pin "40") (pinfunction "PB4_40") (pintype "bidirectional"))
    )
    (net (code "81") (name "unconnected-(U1-PB5-Pad41)") (class "Default")
      (node (ref "U1") (pin "41") (pinfunction "PB5_41") (pintype "bidirectional"))
    )
    (net (code "82") (name "unconnected-(U1-PB8-Pad45)") (class "Default")
      (node (ref "U1") (pin "45") (pinfunction "PB8_45") (pintype "bidirectional"))
    )
    (net (code "83") (name "unconnected-(U1-PB9-Pad46)") (class "Default")
      (node (ref "U1") (pin "46") (pinfunction "PB9_46") (pintype "bidirectional"))
    )
    (net (code "84") (name "unconnected-(U1-PB10-Pad21)") (class "Default")
      (node (ref "U1") (pin "21") (pinfunction "PB10_21") (pintype "bidirectional"))
    )
    (net (code "85") (name "unconnected-(U1-PB11-Pad22)") (class "Default")
      (node (ref "U1") (pin "22") (pinfunction "PB11_22") (pintype "bidirectional"))
    )
    (net (code "86") (name "unconnected-(U1-PC13-Pad2)") (class "Default")
      (node (ref "U1") (pin "2") (pinfunction "PC13_2") (pintype "bidirectional"))
    )
    (net (code "87") (name "unconnected-(U1-PC14-Pad3)") (class "Default")
      (node (ref "U1") (pin "3") (pinfunction "PC14_3") (pintype "bidirectional"))
    )
    (net (code "88") (name "unconnected-(U1-PC15-Pad4)") (class "Default")
      (node (ref "U1") (pin "4") (pinfunction "PC15_4") (pintype "bidirectional"))
    )
    (net (code "89") (name "unconnected-(X2E-S-Pad5)") (class "Default")
      (node (ref "X2") (pin "5") (pinfunction "S_5") (pintype "passive"))
    )
    (net (code "90") (name "unconnected-(X2F-S-Pad6)") (class "Default")
      (node (ref "X2") (pin "6") (pinfunction "S_6") (pintype "passive"))
    )
  )
)
